# TB-S5D5_p04_Connectors-v1_2.net
KiCad netlist of a schematic drawn in Altium Designer
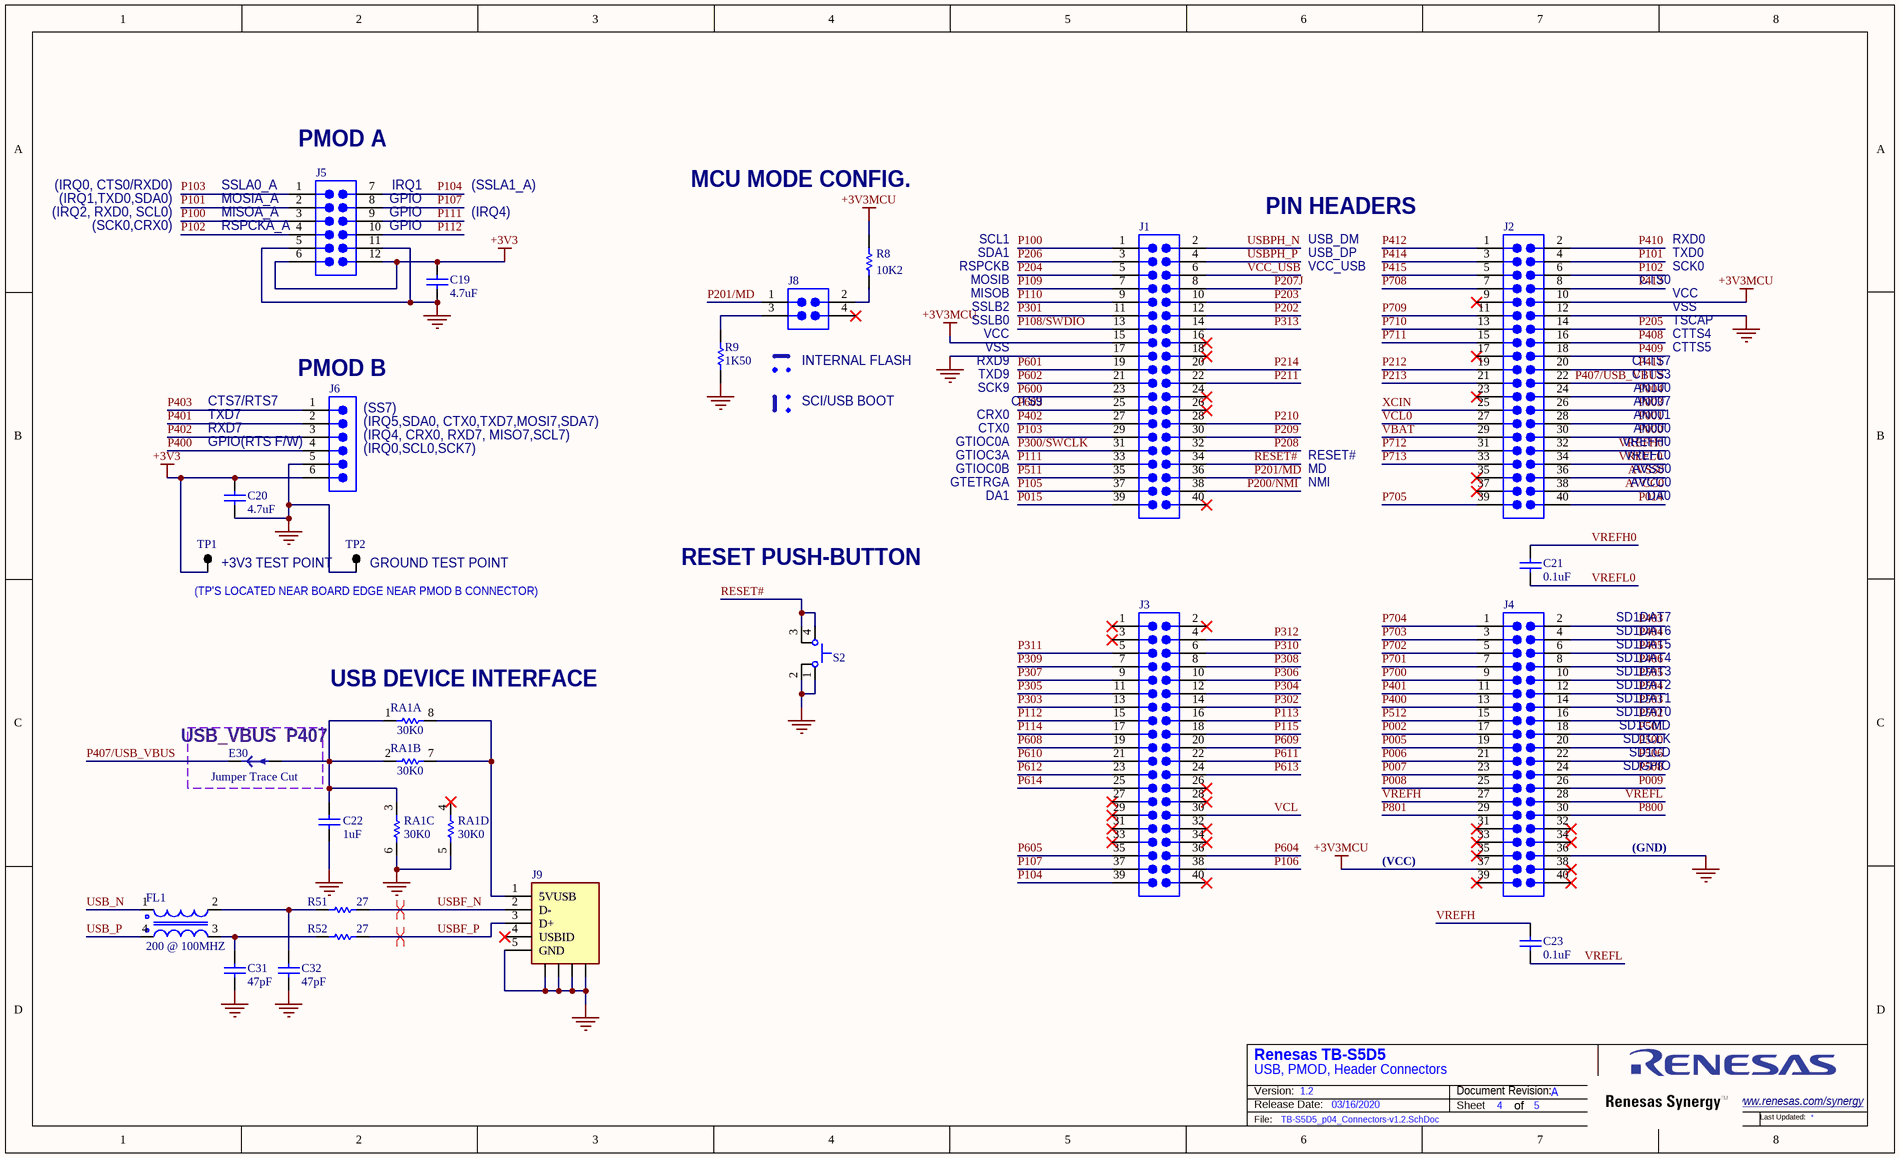
[diagram p0: TB-S5D5_p04_Connectors-v1.2.SchDoc]

(export (version "E")
  (design (tool "Eeschema 10.0.6"))
  (components
    (comp (ref "C19")
      (value "CAP-000043-01")
      (footprint "CAPC0603-01")
      (description "Ceramic Chip Capacitor 0603 4.7uF 6.3V")
      (fields
        (field (name "MANUFACTURER") "Samsung")
        (field (name "MFG PART NUMBER") "CL10A475KQ8NNNL")
        (field (name "CAPACITANCE") "4.7uF")
      )
      (libsource (lib "Capacitors") (part "CAP-000043-01"))
    )
    (comp (ref "C20")
      (value "CAP-000043-01")
      (footprint "CAPC0603-01")
      (description "Ceramic Chip Capacitor 0603 4.7uF 6.3V")
      (fields
        (field (name "MANUFACTURER") "Samsung")
        (field (name "MFG PART NUMBER") "CL10A475KQ8NNNL")
        (field (name "CAPACITANCE") "4.7uF")
      )
      (libsource (lib "Capacitors") (part "CAP-000043-01"))
    )
    (comp (ref "C21")
      (value "CAP-000029-01")
      (footprint "CAPC0603-01")
      (description "Ceramic Chip Capacitor 0603 0.1uF 50V")
      (fields
        (field (name "MANUFACTURER") "Samsung")
        (field (name "MFG PART NUMBER") "CL10B104KB8NNNC")
        (field (name "CAPACITANCE") "0.1uF")
      )
      (libsource (lib "Capacitors") (part "CAP-000029-01"))
    )
    (comp (ref "C22")
      (value "CAP-000063-01")
      (footprint "CAPC0402-01")
      (description "Ceramic Chip Capacitor 0402 1uF 16V")
      (fields
        (field (name "MANUFACTURER") "Samsung")
        (field (name "MFG PART NUMBER") "CL05A105KO5NNNC")
        (field (name "CAPACITANCE") "1uF")
      )
      (libsource (lib "Capacitors") (part "CAP-000063-01"))
    )
    (comp (ref "C23")
      (value "CAP-000029-01")
      (footprint "CAPC0603-01")
      (description "Ceramic Chip Capacitor 0603 0.1uF 50V")
      (fields
        (field (name "MANUFACTURER") "Samsung")
        (field (name "MFG PART NUMBER") "CL10B104KB8NNNC")
        (field (name "CAPACITANCE") "0.1uF")
      )
      (libsource (lib "Capacitors") (part "CAP-000029-01"))
    )
    (comp (ref "C31")
      (value "CAP-000127-01")
      (footprint "CAPC0402-01")
      (description "Ceramic Chip Capacitor 0402 47pF 50V NP0/C0G")
      (fields
        (field (name "MANUFACTURER") "Murata")
        (field (name "MFG PART NUMBER") "GRM1555C1H470JA01D")
        (field (name "CAPACITANCE") "47pF")
      )
      (libsource (lib "DK-S5D9_SpecialParts") (part "CAP-000127-01"))
    )
    (comp (ref "C32")
      (value "CAP-000127-01")
      (footprint "CAPC0402-01")
      (description "Ceramic Chip Capacitor 0402 47pF 50V NP0/C0G")
      (fields
        (field (name "MANUFACTURER") "Murata")
        (field (name "MFG PART NUMBER") "GRM1555C1H470JA01D")
        (field (name "CAPACITANCE") "47pF")
      )
      (libsource (lib "DK-S5D9_SpecialParts") (part "CAP-000127-01"))
    )
    (comp (ref "E30")
      (value "Jumper Trace Cut")
      (footprint "E_PadsTraceCut0805")
      (description "Pads on PCB with Trace Between for Cutting to isolate")
      (libsource (lib "TB_SpecialLib") (part "E_JmpTraceCut"))
    )
    (comp (ref "FL1")
      (value "IND-000027-01")
      (footprint "FL0504")
      (description "Common Mode Filter Inductor, 200 ohm CM @ 100MHz")
      (fields
        (field (name "MANUFACTURER") "Murata")
        (field (name "MFG PART NUMBER") "DLP11SN201HL2L")
        (field (name "RESISTANCE") "200 @ 100MHZ")
      )
      (libsource (lib "DK-S5D9_SpecialParts") (part "IND-000027-01"))
    )
    (comp (ref "J1")
      (value "CON-000109-A1")
      (footprint "J_2x20pHDR100mil")
      (description "Header 0.1\" pitch 40pos 2x20, T<->B Inverted")
      (fields (field (name "MANUFACTURER") "Sullins") (field (name "MFG PART NUMBER") "PRPC020DAAN-RC"))
      (libsource (lib "SpecialPartsLib") (part "CON-000109-A1"))
    )
    (comp (ref "J2")
      (value "CON-000109-A1")
      (footprint "J_2x20pHDR100mil")
      (description "Header 0.1\" pitch 40pos 2x20, T<->B Inverted")
      (fields (field (name "MANUFACTURER") "Sullins") (field (name "MFG PART NUMBER") "PRPC020DAAN-RC"))
      (libsource (lib "SpecialPartsLib") (part "CON-000109-A1"))
    )
    (comp (ref "J3")
      (value "CON-000109-A1")
      (footprint "J_2x20pHDR100mil")
      (description "Header 0.1\" pitch 40pos 2x20, T<->B Inverted")
      (fields (field (name "MANUFACTURER") "Sullins") (field (name "MFG PART NUMBER") "PRPC020DAAN-RC"))
      (libsource (lib "SpecialPartsLib") (part "CON-000109-A1"))
    )
    (comp (ref "J4")
      (value "CON-000109-A1")
      (footprint "J_2x20pHDR100mil")
      (description "Header 0.1\" pitch 40pos 2x20, T<->B Inverted")
      (fields (field (name "MANUFACTURER") "Sullins") (field (name "MFG PART NUMBER") "PRPC020DAAN-RC"))
      (libsource (lib "SpecialPartsLib") (part "CON-000109-A1"))
    )
    (comp (ref "J5")
      (value "CON-000050-01")
      (footprint "SAMTEC_SSW-106-02-F-D-RA-PMOD")
      (description "Samtec Female Header 0.1\" pitch PMOD 2x6 Right Angle")
      (fields (field (name "MANUFACTURER") "Samtec") (field (name "MFG PART NUMBER") "SSW-106-02-F-D-RA"))
      (libsource (lib "Connectors") (part "CON-000050-01_P"))
    )
    (comp (ref "J6")
      (value "CON-000148-01")
      (footprint "SAMTEC_SSW-106-02-F-S-RA")
      (description "Samtec Female Header 0.1\" pitch 6pos 1x6 Right Angle")
      (fields (field (name "MANUFACTURER") "Samtec") (field (name "MFG PART NUMBER") "SSW-106-02-FM-S-RA"))
      (libsource (lib "Connectors") (part "CON-000148-01"))
    )
    (comp (ref "J8")
      (value "CON-000174-01")
      (footprint "FCI_77313-801-04LF")
      (description "FCI Header 0.1\" pitch 4pos 2x2")
      (fields (field (name "MANUFACTURER") "FCI") (field (name "MFG PART NUMBER") "67997-404HLF"))
      (libsource (lib "Connectors") (part "CON-000174-01"))
    )
    (comp (ref "J9")
      (value "CON-000116-01")
      (footprint "FCI_10118192")
      (description "USB Micro 2.0 Female 5 Pin Right Angle")
      (fields (field (name "MANUFACTURER") "FCI") (field (name "MFG PART NUMBER") "10118192-0001LF"))
      (libsource (lib "Connectors") (part "CON-000116-01"))
    )
    (comp (ref "R8")
      (value "RES-000091-01")
      (footprint "RESC0603-01")
      (description "Chip Resistor Thick Film 0603 10K2 1% 1/10W")
      (fields
        (field (name "MANUFACTURER") "NIC")
        (field (name "MFG PART NUMBER") "NRC06F1022TRF")
        (field (name "RESISTANCE") "10K2")
      )
      (libsource (lib "Resistors") (part "RES-000091-01"))
    )
    (comp (ref "R9")
      (value "RES-000140-01")
      (footprint "RESC0402-01")
      (description "Chip Resistor Thick Film 0402 1K50 0.5% 1/16W")
      (fields
        (field (name "MANUFACTURER") "Panasonic")
        (field (name "MFG PART NUMBER") "ERA-2AED152X")
        (field (name "RESISTANCE") "1K50")
      )
      (libsource (lib "Resistors") (part "RES-000140-01"))
    )
    (comp (ref "R51")
      (value "RES-R70620-01")
      (footprint "RESC0603-01")
      (description "Chip Resistor Thick Film 0603 27 5% 1/10W")
      (fields
        (field (name "MANUFACTURER") "Stackpole")
        (field (name "MFG PART NUMBER") "RMCF0603JT27R0")
        (field (name "RESISTANCE") "27")
      )
      (libsource (lib "Resistors") (part "RES-000210-01"))
    )
    (comp (ref "R52")
      (value "RES-R70620-01")
      (footprint "RESC0603-01")
      (description "Chip Resistor Thick Film 0603 27 5% 1/10W")
      (fields
        (field (name "MANUFACTURER") "Stackpole")
        (field (name "MFG PART NUMBER") "RMCF0603JT27R0")
        (field (name "RESISTANCE") "27")
      )
      (libsource (lib "Resistors") (part "RES-000210-01"))
    )
    (comp (ref "RA1")
      (value "RES-000117-01")
      (footprint "RESCAF0804")
      (description "Chip Resistor Array 0804 30K0 5% 1/16W 4 x 0402")
      (fields
        (field (name "MANUFACTURER") "Panasonic")
        (field (name "MFG PART NUMBER") "EXB-28V303JX")
        (field (name "RESISTANCE") "30K0")
      )
      (libsource (lib "Resistors") (part "RES-000117-01"))
    )
    (comp (ref "S2")
      (value "SWT-000013-01")
      (footprint "SW_C&K_PTS645_43")
      (description "Push Button Switch 6 x 6mm 4.3mm High")
      (fields (field (name "MANUFACTURER") "C&K") (field (name "MFG PART NUMBER") "PTS645SM43SMTR92 LFS"))
      (libsource (lib "Misc") (part "SWT-000013-01"))
    )
    (comp (ref "TP1")
      (value "Test Point")
      (footprint "TP_40milTHpad")
      (description "Test Point, Through Hole Pad 40mil ID")
      (libsource (lib "TB_SpecialLib") (part "TP_TH"))
    )
    (comp (ref "TP2")
      (value "Test Point")
      (footprint "TP_40milTHpad")
      (description "Test Point, Through Hole Pad 40mil ID")
      (libsource (lib "TB_SpecialLib") (part "TP_TH"))
    )
  )
  (nets
    (net (code "1") (name "+3V3") (class "Default")
      (node (ref "C19") (pin "2") (pinfunction "2_2") (pintype "passive"))
      (node (ref "C20") (pin "2") (pinfunction "2_2") (pintype "passive"))
      (node (ref "J5") (pin "12") (pinfunction "12_12") (pintype "passive"))
      (node (ref "J5") (pin "6") (pinfunction "6_6") (pintype "passive"))
      (node (ref "J6") (pin "6") (pinfunction "6_6") (pintype "passive"))
      (node (ref "TP1") (pin "1") (pinfunction "TP_1") (pintype "passive"))
    )
    (net (code "2") (name "+3V3MCU") (class "Default")
      (node (ref "J1") (pin "15") (pinfunction "15_15") (pintype "passive"))
      (node (ref "J2") (pin "10") (pinfunction "10_10") (pintype "passive"))
      (node (ref "J4") (pin "37") (pinfunction "37_37") (pintype "passive"))
      (node (ref "R8") (pin "2") (pinfunction "2_2") (pintype "passive"))
    )
    (net (code "3") (name "/AVCC0") (class "Default")
      (node (ref "J2") (pin "38") (pinfunction "38_38") (pintype "passive"))
    )
    (net (code "4") (name "/AVSS0") (class "Default")
      (node (ref "J2") (pin "36") (pinfunction "36_36") (pintype "passive"))
    )
    (net (code "5") (name "/P000") (class "Default")
      (node (ref "J2") (pin "30") (pinfunction "30_30") (pintype "passive"))
    )
    (net (code "6") (name "/P001") (class "Default")
      (node (ref "J2") (pin "28") (pinfunction "28_28") (pintype "passive"))
    )
    (net (code "7") (name "/P002") (class "Default")
      (node (ref "J4") (pin "17") (pinfunction "17_17") (pintype "passive"))
    )
    (net (code "8") (name "/P003") (class "Default")
      (node (ref "J2") (pin "26") (pinfunction "26_26") (pintype "passive"))
    )
    (net (code "9") (name "/P004") (class "Default")
      (node (ref "J2") (pin "24") (pinfunction "24_24") (pintype "passive"))
    )
    (net (code "10") (name "/P005") (class "Default")
      (node (ref "J4") (pin "19") (pinfunction "19_19") (pintype "passive"))
    )
    (net (code "11") (name "/P006") (class "Default")
      (node (ref "J4") (pin "21") (pinfunction "21_21") (pintype "passive"))
    )
    (net (code "12") (name "/P007") (class "Default")
      (node (ref "J4") (pin "23") (pinfunction "23_23") (pintype "passive"))
    )
    (net (code "13") (name "/P008") (class "Default")
      (node (ref "J4") (pin "25") (pinfunction "25_25") (pintype "passive"))
    )
    (net (code "14") (name "/P009") (class "Default")
      (node (ref "J4") (pin "26") (pinfunction "26_26") (pintype "passive"))
    )
    (net (code "15") (name "/P014") (class "Default")
      (node (ref "J2") (pin "40") (pinfunction "40_40") (pintype "passive"))
    )
    (net (code "16") (name "/P015") (class "Default")
      (node (ref "J1") (pin "39") (pinfunction "39_39") (pintype "passive"))
    )
    (net (code "17") (name "/P100") (class "Default")
      (node (ref "J1") (pin "1") (pinfunction "1_1") (pintype "passive"))
      (node (ref "J5") (pin "3") (pinfunction "3_3") (pintype "passive"))
    )
    (net (code "18") (name "/P101") (class "Default")
      (node (ref "J2") (pin "4") (pinfunction "4_4") (pintype "passive"))
      (node (ref "J5") (pin "2") (pinfunction "2_2") (pintype "passive"))
    )
    (net (code "19") (name "/P102") (class "Default")
      (node (ref "J2") (pin "6") (pinfunction "6_6") (pintype "passive"))
      (node (ref "J5") (pin "4") (pinfunction "4_4") (pintype "passive"))
    )
    (net (code "20") (name "/P103") (class "Default")
      (node (ref "J1") (pin "29") (pinfunction "29_29") (pintype "passive"))
      (node (ref "J5") (pin "1") (pinfunction "1_1") (pintype "passive"))
    )
    (net (code "21") (name "/P104") (class "Default")
      (node (ref "J3") (pin "39") (pinfunction "39_39") (pintype "passive"))
      (node (ref "J5") (pin "7") (pinfunction "7_7") (pintype "passive"))
    )
    (net (code "22") (name "/P105") (class "Default")
      (node (ref "J1") (pin "37") (pinfunction "37_37") (pintype "passive"))
    )
    (net (code "23") (name "/P106") (class "Default")
      (node (ref "J3") (pin "38") (pinfunction "38_38") (pintype "passive"))
    )
    (net (code "24") (name "/P107") (class "Default")
      (node (ref "J3") (pin "37") (pinfunction "37_37") (pintype "passive"))
      (node (ref "J5") (pin "8") (pinfunction "8_8") (pintype "passive"))
    )
    (net (code "25") (name "/P108{slash}SWDIO") (class "Default")
      (node (ref "J1") (pin "13") (pinfunction "13_13") (pintype "passive"))
    )
    (net (code "26") (name "/P109") (class "Default")
      (node (ref "J1") (pin "7") (pinfunction "7_7") (pintype "passive"))
    )
    (net (code "27") (name "/P110") (class "Default")
      (node (ref "J1") (pin "9") (pinfunction "9_9") (pintype "passive"))
    )
    (net (code "28") (name "/P111") (class "Default")
      (node (ref "J1") (pin "33") (pinfunction "33_33") (pintype "passive"))
      (node (ref "J5") (pin "9") (pinfunction "9_9") (pintype "passive"))
    )
    (net (code "29") (name "/P112") (class "Default")
      (node (ref "J3") (pin "15") (pinfunction "15_15") (pintype "passive"))
      (node (ref "J5") (pin "10") (pinfunction "10_10") (pintype "passive"))
    )
    (net (code "30") (name "/P113") (class "Default")
      (node (ref "J3") (pin "16") (pinfunction "16_16") (pintype "passive"))
    )
    (net (code "31") (name "/P114") (class "Default")
      (node (ref "J3") (pin "17") (pinfunction "17_17") (pintype "passive"))
    )
    (net (code "32") (name "/P115") (class "Default")
      (node (ref "J3") (pin "18") (pinfunction "18_18") (pintype "passive"))
    )
    (net (code "33") (name "/P200{slash}NMI") (class "Default")
      (node (ref "J1") (pin "38") (pinfunction "38_38") (pintype "passive"))
    )
    (net (code "34") (name "/P201{slash}MD") (class "Default")
      (node (ref "J1") (pin "36") (pinfunction "36_36") (pintype "passive"))
      (node (ref "J8") (pin "1") (pinfunction "1_1") (pintype "passive"))
    )
    (net (code "35") (name "/P202") (class "Default")
      (node (ref "J1") (pin "12") (pinfunction "12_12") (pintype "passive"))
    )
    (net (code "36") (name "/P203") (class "Default")
      (node (ref "J1") (pin "10") (pinfunction "10_10") (pintype "passive"))
    )
    (net (code "37") (name "/P204") (class "Default")
      (node (ref "J1") (pin "5") (pinfunction "5_5") (pintype "passive"))
    )
    (net (code "38") (name "/P205") (class "Default")
      (node (ref "J2") (pin "14") (pinfunction "14_14") (pintype "passive"))
    )
    (net (code "39") (name "/P206") (class "Default")
      (node (ref "J1") (pin "3") (pinfunction "3_3") (pintype "passive"))
    )
    (net (code "40") (name "/P207J") (class "Default")
      (node (ref "J1") (pin "8") (pinfunction "8_8") (pintype "passive"))
    )
    (net (code "41") (name "/P208") (class "Default")
      (node (ref "J1") (pin "32") (pinfunction "32_32") (pintype "passive"))
    )
    (net (code "42") (name "/P209") (class "Default")
      (node (ref "J1") (pin "30") (pinfunction "30_30") (pintype "passive"))
    )
    (net (code "43") (name "/P210") (class "Default")
      (node (ref "J1") (pin "28") (pinfunction "28_28") (pintype "passive"))
    )
    (net (code "44") (name "/P211") (class "Default")
      (node (ref "J1") (pin "22") (pinfunction "22_22") (pintype "passive"))
    )
    (net (code "45") (name "/P212") (class "Default")
      (node (ref "J2") (pin "19") (pinfunction "19_19") (pintype "passive"))
    )
    (net (code "46") (name "/P213") (class "Default")
      (node (ref "J2") (pin "21") (pinfunction "21_21") (pintype "passive"))
    )
    (net (code "47") (name "/P214") (class "Default")
      (node (ref "J1") (pin "20") (pinfunction "20_20") (pintype "passive"))
    )
    (net (code "48") (name "/P300{slash}SWCLK") (class "Default")
      (node (ref "J1") (pin "31") (pinfunction "31_31") (pintype "passive"))
    )
    (net (code "49") (name "/P301") (class "Default")
      (node (ref "J1") (pin "11") (pinfunction "11_11") (pintype "passive"))
    )
    (net (code "50") (name "/P302") (class "Default")
      (node (ref "J3") (pin "14") (pinfunction "14_14") (pintype "passive"))
    )
    (net (code "51") (name "/P303") (class "Default")
      (node (ref "J3") (pin "13") (pinfunction "13_13") (pintype "passive"))
    )
    (net (code "52") (name "/P304") (class "Default")
      (node (ref "J3") (pin "12") (pinfunction "12_12") (pintype "passive"))
    )
    (net (code "53") (name "/P305") (class "Default")
      (node (ref "J3") (pin "11") (pinfunction "11_11") (pintype "passive"))
    )
    (net (code "54") (name "/P306") (class "Default")
      (node (ref "J3") (pin "10") (pinfunction "10_10") (pintype "passive"))
    )
    (net (code "55") (name "/P307") (class "Default")
      (node (ref "J3") (pin "9") (pinfunction "9_9") (pintype "passive"))
    )
    (net (code "56") (name "/P308") (class "Default")
      (node (ref "J3") (pin "8") (pinfunction "8_8") (pintype "passive"))
    )
    (net (code "57") (name "/P309") (class "Default")
      (node (ref "J3") (pin "7") (pinfunction "7_7") (pintype "passive"))
    )
    (net (code "58") (name "/P310") (class "Default")
      (node (ref "J3") (pin "6") (pinfunction "6_6") (pintype "passive"))
    )
    (net (code "59") (name "/P311") (class "Default")
      (node (ref "J3") (pin "5") (pinfunction "5_5") (pintype "passive"))
    )
    (net (code "60") (name "/P312") (class "Default")
      (node (ref "J3") (pin "4") (pinfunction "4_4") (pintype "passive"))
    )
    (net (code "61") (name "/P313") (class "Default")
      (node (ref "J1") (pin "14") (pinfunction "14_14") (pintype "passive"))
    )
    (net (code "62") (name "/P400") (class "Default")
      (node (ref "J4") (pin "13") (pinfunction "13_13") (pintype "passive"))
      (node (ref "J6") (pin "4") (pinfunction "4_4") (pintype "passive"))
    )
    (net (code "63") (name "/P401") (class "Default")
      (node (ref "J4") (pin "11") (pinfunction "11_11") (pintype "passive"))
      (node (ref "J6") (pin "2") (pinfunction "2_2") (pintype "passive"))
    )
    (net (code "64") (name "/P402") (class "Default")
      (node (ref "J1") (pin "27") (pinfunction "27_27") (pintype "passive"))
      (node (ref "J6") (pin "3") (pinfunction "3_3") (pintype "passive"))
    )
    (net (code "65") (name "/P403") (class "Default")
      (node (ref "J4") (pin "2") (pinfunction "2_2") (pintype "passive"))
      (node (ref "J6") (pin "1") (pinfunction "1_1") (pintype "passive"))
    )
    (net (code "66") (name "/P404") (class "Default")
      (node (ref "J4") (pin "4") (pinfunction "4_4") (pintype "passive"))
    )
    (net (code "67") (name "/P405") (class "Default")
      (node (ref "J4") (pin "6") (pinfunction "6_6") (pintype "passive"))
    )
    (net (code "68") (name "/P406") (class "Default")
      (node (ref "J4") (pin "8") (pinfunction "8_8") (pintype "passive"))
    )
    (net (code "69") (name "/P407{slash}USB_VBUS") (class "Default")
      (node (ref "E30") (pin "1") (pinfunction "A_1") (pintype "passive"))
      (node (ref "J2") (pin "22") (pinfunction "22_22") (pintype "passive"))
    )
    (net (code "70") (name "/P408") (class "Default")
      (node (ref "J2") (pin "16") (pinfunction "16_16") (pintype "passive"))
    )
    (net (code "71") (name "/P409") (class "Default")
      (node (ref "J2") (pin "18") (pinfunction "18_18") (pintype "passive"))
    )
    (net (code "72") (name "/P410") (class "Default")
      (node (ref "J2") (pin "2") (pinfunction "2_2") (pintype "passive"))
    )
    (net (code "73") (name "/P411") (class "Default")
      (node (ref "J2") (pin "20") (pinfunction "20_20") (pintype "passive"))
    )
    (net (code "74") (name "/P412") (class "Default")
      (node (ref "J2") (pin "1") (pinfunction "1_1") (pintype "passive"))
    )
    (net (code "75") (name "/P413") (class "Default")
      (node (ref "J2") (pin "8") (pinfunction "8_8") (pintype "passive"))
    )
    (net (code "76") (name "/P414") (class "Default")
      (node (ref "J2") (pin "3") (pinfunction "3_3") (pintype "passive"))
    )
    (net (code "77") (name "/P415") (class "Default")
      (node (ref "J2") (pin "5") (pinfunction "5_5") (pintype "passive"))
    )
    (net (code "78") (name "/P500") (class "Default")
      (node (ref "J4") (pin "20") (pinfunction "20_20") (pintype "passive"))
    )
    (net (code "79") (name "/P501") (class "Default")
      (node (ref "J4") (pin "18") (pinfunction "18_18") (pintype "passive"))
    )
    (net (code "80") (name "/P502") (class "Default")
      (node (ref "J4") (pin "16") (pinfunction "16_16") (pintype "passive"))
    )
    (net (code "81") (name "/P503") (class "Default")
      (node (ref "J4") (pin "14") (pinfunction "14_14") (pintype "passive"))
    )
    (net (code "82") (name "/P504") (class "Default")
      (node (ref "J4") (pin "12") (pinfunction "12_12") (pintype "passive"))
    )
    (net (code "83") (name "/P505") (class "Default")
      (node (ref "J4") (pin "10") (pinfunction "10_10") (pintype "passive"))
    )
    (net (code "84") (name "/P506") (class "Default")
      (node (ref "J4") (pin "22") (pinfunction "22_22") (pintype "passive"))
    )
    (net (code "85") (name "/P508") (class "Default")
      (node (ref "J4") (pin "24") (pinfunction "24_24") (pintype "passive"))
    )
    (net (code "86") (name "/P511") (class "Default")
      (node (ref "J1") (pin "35") (pinfunction "35_35") (pintype "passive"))
    )
    (net (code "87") (name "/P512") (class "Default")
      (node (ref "J4") (pin "15") (pinfunction "15_15") (pintype "passive"))
    )
    (net (code "88") (name "/P600") (class "Default")
      (node (ref "J1") (pin "23") (pinfunction "23_23") (pintype "passive"))
    )
    (net (code "89") (name "/P601") (class "Default")
      (node (ref "J1") (pin "19") (pinfunction "19_19") (pintype "passive"))
    )
    (net (code "90") (name "/P602") (class "Default")
      (node (ref "J1") (pin "21") (pinfunction "21_21") (pintype "passive"))
    )
    (net (code "91") (name "/P603") (class "Default")
      (node (ref "J1") (pin "25") (pinfunction "25_25") (pintype "passive"))
    )
    (net (code "92") (name "/P604") (class "Default")
      (node (ref "J3") (pin "36") (pinfunction "36_36") (pintype "passive"))
    )
    (net (code "93") (name "/P605") (class "Default")
      (node (ref "J3") (pin "35") (pinfunction "35_35") (pintype "passive"))
    )
    (net (code "94") (name "/P608") (class "Default")
      (node (ref "J3") (pin "19") (pinfunction "19_19") (pintype "passive"))
    )
    (net (code "95") (name "/P609") (class "Default")
      (node (ref "J3") (pin "20") (pinfunction "20_20") (pintype "passive"))
    )
    (net (code "96") (name "/P610") (class "Default")
      (node (ref "J3") (pin "21") (pinfunction "21_21") (pintype "passive"))
    )
    (net (code "97") (name "/P611") (class "Default")
      (node (ref "J3") (pin "22") (pinfunction "22_22") (pintype "passive"))
    )
    (net (code "98") (name "/P612") (class "Default")
      (node (ref "J3") (pin "23") (pinfunction "23_23") (pintype "passive"))
    )
    (net (code "99") (name "/P613") (class "Default")
      (node (ref "J3") (pin "24") (pinfunction "24_24") (pintype "passive"))
    )
    (net (code "100") (name "/P614") (class "Default")
      (node (ref "J3") (pin "25") (pinfunction "25_25") (pintype "passive"))
    )
    (net (code "101") (name "/P700") (class "Default")
      (node (ref "J4") (pin "9") (pinfunction "9_9") (pintype "passive"))
    )
    (net (code "102") (name "/P701") (class "Default")
      (node (ref "J4") (pin "7") (pinfunction "7_7") (pintype "passive"))
    )
    (net (code "103") (name "/P702") (class "Default")
      (node (ref "J4") (pin "5") (pinfunction "5_5") (pintype "passive"))
    )
    (net (code "104") (name "/P703") (class "Default")
      (node (ref "J4") (pin "3") (pinfunction "3_3") (pintype "passive"))
    )
    (net (code "105") (name "/P704") (class "Default")
      (node (ref "J4") (pin "1") (pinfunction "1_1") (pintype "passive"))
    )
    (net (code "106") (name "/P705") (class "Default")
      (node (ref "J2") (pin "39") (pinfunction "39_39") (pintype "passive"))
    )
    (net (code "107") (name "/P708") (class "Default")
      (node (ref "J2") (pin "7") (pinfunction "7_7") (pintype "passive"))
    )
    (net (code "108") (name "/P709") (class "Default")
      (node (ref "J2") (pin "11") (pinfunction "11_11") (pintype "passive"))
    )
    (net (code "109") (name "/P710") (class "Default")
      (node (ref "J2") (pin "13") (pinfunction "13_13") (pintype "passive"))
    )
    (net (code "110") (name "/P711") (class "Default")
      (node (ref "J2") (pin "15") (pinfunction "15_15") (pintype "passive"))
    )
    (net (code "111") (name "/P712") (class "Default")
      (node (ref "J2") (pin "31") (pinfunction "31_31") (pintype "passive"))
    )
    (net (code "112") (name "/P713") (class "Default")
      (node (ref "J2") (pin "33") (pinfunction "33_33") (pintype "passive"))
    )
    (net (code "113") (name "/P800") (class "Default")
      (node (ref "J4") (pin "30") (pinfunction "30_30") (pintype "passive"))
    )
    (net (code "114") (name "/P801") (class "Default")
      (node (ref "J4") (pin "29") (pinfunction "29_29") (pintype "passive"))
    )
    (net (code "115") (name "/RESET#") (class "Default")
      (node (ref "J1") (pin "34") (pinfunction "34_34") (pintype "passive"))
      (node (ref "S2") (pin "3") (pinfunction "3_3") (pintype "passive"))
      (node (ref "S2") (pin "4") (pinfunction "4_4") (pintype "passive"))
    )
    (net (code "116") (name "/USBF_N") (class "Default")
      (node (ref "J9") (pin "2") (pinfunction "D-_2") (pintype "passive"))
      (node (ref "R51") (pin "2") (pinfunction "2_2") (pintype "passive"))
    )
    (net (code "117") (name "/USBF_P") (class "Default")
      (node (ref "J9") (pin "3") (pinfunction "D+_3") (pintype "passive"))
      (node (ref "R52") (pin "2") (pinfunction "2_2") (pintype "passive"))
    )
    (net (code "118") (name "/USBPH_N") (class "Default")
      (node (ref "J1") (pin "2") (pinfunction "2_2") (pintype "passive"))
    )
    (net (code "119") (name "/USBPH_P") (class "Default")
      (node (ref "J1") (pin "4") (pinfunction "4_4") (pintype "passive"))
    )
    (net (code "120") (name "/USB_N") (class "Default")
      (node (ref "FL1") (pin "1") (pinfunction "1_1") (pintype "passive"))
    )
    (net (code "121") (name "/USB_P") (class "Default")
      (node (ref "FL1") (pin "4") (pinfunction "4_4") (pintype "passive"))
    )
    (net (code "122") (name "/VBAT") (class "Default")
      (node (ref "J2") (pin "29") (pinfunction "29_29") (pintype "passive"))
    )
    (net (code "123") (name "/VCC_USB") (class "Default")
      (node (ref "J1") (pin "6") (pinfunction "6_6") (pintype "passive"))
    )
    (net (code "124") (name "/VCL") (class "Default")
      (node (ref "J3") (pin "30") (pinfunction "30_30") (pintype "passive"))
    )
    (net (code "125") (name "/VCL0") (class "Default")
      (node (ref "J2") (pin "27") (pinfunction "27_27") (pintype "passive"))
    )
    (net (code "126") (name "/VREFH") (class "Default")
      (node (ref "C23") (pin "2") (pinfunction "2_2") (pintype "passive"))
      (node (ref "J4") (pin "27") (pinfunction "27_27") (pintype "passive"))
    )
    (net (code "127") (name "/VREFH0") (class "Default")
      (node (ref "C21") (pin "2") (pinfunction "2_2") (pintype "passive"))
      (node (ref "J2") (pin "32") (pinfunction "32_32") (pintype "passive"))
    )
    (net (code "128") (name "/VREFL") (class "Default")
      (node (ref "C23") (pin "1") (pinfunction "1_1") (pintype "passive"))
      (node (ref "J4") (pin "28") (pinfunction "28_28") (pintype "passive"))
    )
    (net (code "129") (name "/VREFL0") (class "Default")
      (node (ref "C21") (pin "1") (pinfunction "1_1") (pintype "passive"))
      (node (ref "J2") (pin "34") (pinfunction "34_34") (pintype "passive"))
    )
    (net (code "130") (name "/XCIN") (class "Default")
      (node (ref "J2") (pin "25") (pinfunction "25_25") (pintype "passive"))
    )
    (net (code "131") (name "GND") (class "Default")
      (node (ref "C19") (pin "1") (pinfunction "1_1") (pintype "passive"))
      (node (ref "C20") (pin "1") (pinfunction "1_1") (pintype "passive"))
      (node (ref "C22") (pin "1") (pinfunction "1_1") (pintype "passive"))
      (node (ref "C31") (pin "1") (pinfunction "1_1") (pintype "passive"))
      (node (ref "C32") (pin "1") (pinfunction "1_1") (pintype "passive"))
      (node (ref "J1") (pin "17") (pinfunction "17_17") (pintype "passive"))
      (node (ref "J2") (pin "12") (pinfunction "12_12") (pintype "passive"))
      (node (ref "J4") (pin "36") (pinfunction "36_36") (pintype "passive"))
      (node (ref "J5") (pin "11") (pinfunction "11_11") (pintype "passive"))
      (node (ref "J5") (pin "5") (pinfunction "5_5") (pintype "passive"))
      (node (ref "J6") (pin "5") (pinfunction "5_5") (pintype "passive"))
      (node (ref "J9") (pin "5") (pinfunction "GND_5") (pintype "passive"))
      (node (ref "J9") (pin "C1") (pinfunction "C1_C1") (pintype "passive"))
      (node (ref "J9") (pin "C2") (pinfunction "C2_C2") (pintype "passive"))
      (node (ref "J9") (pin "C3") (pinfunction "C3_C3") (pintype "passive"))
      (node (ref "J9") (pin "C4") (pinfunction "C4_C4") (pintype "passive"))
      (node (ref "R9") (pin "1") (pinfunction "1_1") (pintype "passive"))
      (node (ref "RA1") (pin "5") (pinfunction "5_5") (pintype "passive"))
      (node (ref "RA1") (pin "6") (pinfunction "6_6") (pintype "passive"))
      (node (ref "S2") (pin "1") (pinfunction "1_1") (pintype "passive"))
      (node (ref "S2") (pin "2") (pinfunction "2_2") (pintype "passive"))
      (node (ref "TP2") (pin "1") (pinfunction "TP_1") (pintype "passive"))
    )
    (net (code "132") (name "Net-(C22-Pad2)") (class "Default")
      (node (ref "C22") (pin "2") (pinfunction "2_2") (pintype "passive"))
      (node (ref "E30") (pin "2") (pinfunction "A_2") (pintype "passive"))
      (node (ref "RA1") (pin "1") (pinfunction "1_1") (pintype "passive"))
      (node (ref "RA1") (pin "2") (pinfunction "2_2") (pintype "passive"))
      (node (ref "RA1") (pin "3") (pinfunction "3_3") (pintype "passive"))
    )
    (net (code "133") (name "Net-(C31-Pad2)") (class "Default")
      (node (ref "C31") (pin "2") (pinfunction "2_2") (pintype "passive"))
      (node (ref "FL1") (pin "3") (pinfunction "3_3") (pintype "passive"))
      (node (ref "R52") (pin "1") (pinfunction "1_1") (pintype "passive"))
    )
    (net (code "134") (name "Net-(C32-Pad2)") (class "Default")
      (node (ref "C32") (pin "2") (pinfunction "2_2") (pintype "passive"))
      (node (ref "FL1") (pin "2") (pinfunction "2_2") (pintype "passive"))
      (node (ref "R51") (pin "1") (pinfunction "1_1") (pintype "passive"))
    )
    (net (code "135") (name "Net-(J8-Pad2)") (class "Default")
      (node (ref "J8") (pin "2") (pinfunction "2_2") (pintype "passive"))
      (node (ref "R8") (pin "1") (pinfunction "1_1") (pintype "passive"))
    )
    (net (code "136") (name "Net-(J8-Pad3)") (class "Default")
      (node (ref "J8") (pin "3") (pinfunction "3_3") (pintype "passive"))
      (node (ref "R9") (pin "2") (pinfunction "2_2") (pintype "passive"))
    )
    (net (code "137") (name "Net-(J9-5VUSB)") (class "Default")
      (node (ref "J9") (pin "1") (pinfunction "5VUSB_1") (pintype "passive"))
      (node (ref "RA1") (pin "7") (pinfunction "7_7") (pintype "passive"))
      (node (ref "RA1") (pin "8") (pinfunction "8_8") (pintype "passive"))
    )
    (net (code "138") (name "unconnected-(J1-Pad16)") (class "Default")
      (node (ref "J1") (pin "16") (pinfunction "16_16") (pintype "passive+no_connect"))
    )
    (net (code "139") (name "unconnected-(J1-Pad18)") (class "Default")
      (node (ref "J1") (pin "18") (pinfunction "18_18") (pintype "passive+no_connect"))
    )
    (net (code "140") (name "unconnected-(J1-Pad24)") (class "Default")
      (node (ref "J1") (pin "24") (pinfunction "24_24") (pintype "passive+no_connect"))
    )
    (net (code "141") (name "unconnected-(J1-Pad26)") (class "Default")
      (node (ref "J1") (pin "26") (pinfunction "26_26") (pintype "passive+no_connect"))
    )
    (net (code "142") (name "unconnected-(J1-Pad40)") (class "Default")
      (node (ref "J1") (pin "40") (pinfunction "40_40") (pintype "passive+no_connect"))
    )
    (net (code "143") (name "unconnected-(J2-Pad9)") (class "Default")
      (node (ref "J2") (pin "9") (pinfunction "9_9") (pintype "passive+no_connect"))
    )
    (net (code "144") (name "unconnected-(J2-Pad17)") (class "Default")
      (node (ref "J2") (pin "17") (pinfunction "17_17") (pintype "passive+no_connect"))
    )
    (net (code "145") (name "unconnected-(J2-Pad23)") (class "Default")
      (node (ref "J2") (pin "23") (pinfunction "23_23") (pintype "passive+no_connect"))
    )
    (net (code "146") (name "unconnected-(J2-Pad35)") (class "Default")
      (node (ref "J2") (pin "35") (pinfunction "35_35") (pintype "passive+no_connect"))
    )
    (net (code "147") (name "unconnected-(J2-Pad37)") (class "Default")
      (node (ref "J2") (pin "37") (pinfunction "37_37") (pintype "passive+no_connect"))
    )
    (net (code "148") (name "unconnected-(J3-Pad1)") (class "Default")
      (node (ref "J3") (pin "1") (pinfunction "1_1") (pintype "passive+no_connect"))
    )
    (net (code "149") (name "unconnected-(J3-Pad2)") (class "Default")
      (node (ref "J3") (pin "2") (pinfunction "2_2") (pintype "passive+no_connect"))
    )
    (net (code "150") (name "unconnected-(J3-Pad3)") (class "Default")
      (node (ref "J3") (pin "3") (pinfunction "3_3") (pintype "passive+no_connect"))
    )
    (net (code "151") (name "unconnected-(J3-Pad26)") (class "Default")
      (node (ref "J3") (pin "26") (pinfunction "26_26") (pintype "passive+no_connect"))
    )
    (net (code "152") (name "unconnected-(J3-Pad27)") (class "Default")
      (node (ref "J3") (pin "27") (pinfunction "27_27") (pintype "passive+no_connect"))
    )
    (net (code "153") (name "unconnected-(J3-Pad28)") (class "Default")
      (node (ref "J3") (pin "28") (pinfunction "28_28") (pintype "passive+no_connect"))
    )
    (net (code "154") (name "unconnected-(J3-Pad29)") (class "Default")
      (node (ref "J3") (pin "29") (pinfunction "29_29") (pintype "passive+no_connect"))
    )
    (net (code "155") (name "unconnected-(J3-Pad31)") (class "Default")
      (node (ref "J3") (pin "31") (pinfunction "31_31") (pintype "passive+no_connect"))
    )
    (net (code "156") (name "unconnected-(J3-Pad32)") (class "Default")
      (node (ref "J3") (pin "32") (pinfunction "32_32") (pintype "passive+no_connect"))
    )
    (net (code "157") (name "unconnected-(J3-Pad33)") (class "Default")
      (node (ref "J3") (pin "33") (pinfunction "33_33") (pintype "passive+no_connect"))
    )
    (net (code "158") (name "unconnected-(J3-Pad34)") (class "Default")
      (node (ref "J3") (pin "34") (pinfunction "34_34") (pintype "passive+no_connect"))
    )
    (net (code "159") (name "unconnected-(J3-Pad40)") (class "Default")
      (node (ref "J3") (pin "40") (pinfunction "40_40") (pintype "passive+no_connect"))
    )
    (net (code "160") (name "unconnected-(J4-Pad31)") (class "Default")
      (node (ref "J4") (pin "31") (pinfunction "31_31") (pintype "passive+no_connect"))
    )
    (net (code "161") (name "unconnected-(J4-Pad32)") (class "Default")
      (node (ref "J4") (pin "32") (pinfunction "32_32") (pintype "passive+no_connect"))
    )
    (net (code "162") (name "unconnected-(J4-Pad33)") (class "Default")
      (node (ref "J4") (pin "33") (pinfunction "33_33") (pintype "passive+no_connect"))
    )
    (net (code "163") (name "unconnected-(J4-Pad34)") (class "Default")
      (node (ref "J4") (pin "34") (pinfunction "34_34") (pintype "passive+no_connect"))
    )
    (net (code "164") (name "unconnected-(J4-Pad35)") (class "Default")
      (node (ref "J4") (pin "35") (pinfunction "35_35") (pintype "passive+no_connect"))
    )
    (net (code "165") (name "unconnected-(J4-Pad38)") (class "Default")
      (node (ref "J4") (pin "38") (pinfunction "38_38") (pintype "passive+no_connect"))
    )
    (net (code "166") (name "unconnected-(J4-Pad39)") (class "Default")
      (node (ref "J4") (pin "39") (pinfunction "39_39") (pintype "passive+no_connect"))
    )
    (net (code "167") (name "unconnected-(J4-Pad40)") (class "Default")
      (node (ref "J4") (pin "40") (pinfunction "40_40") (pintype "passive+no_connect"))
    )
    (net (code "168") (name "unconnected-(J8-Pad4)") (class "Default")
      (node (ref "J8") (pin "4") (pinfunction "4_4") (pintype "passive+no_connect"))
    )
    (net (code "169") (name "unconnected-(J9-USBID-Pad4)") (class "Default")
      (node (ref "J9") (pin "4") (pinfunction "USBID_4") (pintype "passive+no_connect"))
    )
    (net (code "170") (name "unconnected-(RA1-Pad4)") (class "Default")
      (node (ref "RA1") (pin "4") (pinfunction "4_4") (pintype "passive+no_connect"))
    )
  )
)
